# core.net
KiCad netlist of a schematic drawn in Altium Designer
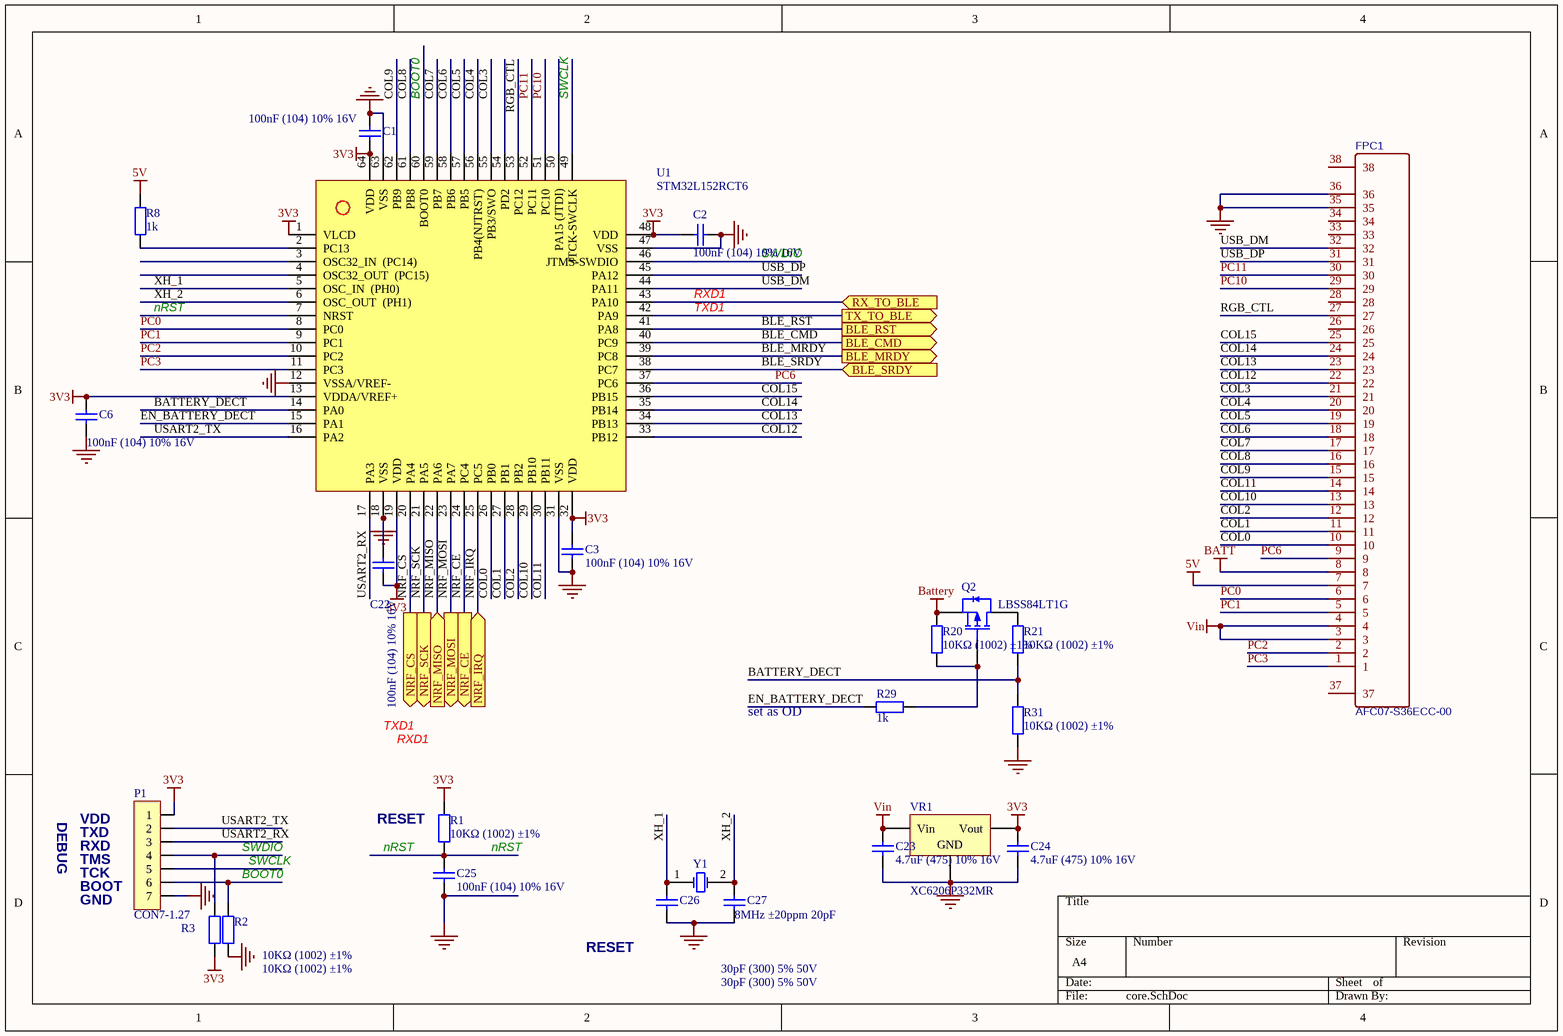
[diagram p0: core.SchDoc]

(export (version "E")
  (design (tool "Eeschema 10.0.6"))
  (components
    (comp (ref "C1")
      (value "100nF (104) 10% 16V")
      (footprint "0402_C")
      (description "贴片电容")
      (libsource (lib "Miscellaneous Devices LC") (part "0402 100nF (104) 10% 16V"))
    )
    (comp (ref "C2")
      (value "100nF (104) 10% 16V")
      (footprint "0402_C")
      (description "贴片电容")
      (libsource (lib "Miscellaneous Devices LC") (part "0402 100nF (104) 10% 16V"))
    )
    (comp (ref "C3")
      (value "100nF (104) 10% 16V")
      (footprint "0402_C")
      (description "贴片电容")
      (libsource (lib "Miscellaneous Devices LC") (part "0402 100nF (104) 10% 16V"))
    )
    (comp (ref "C6")
      (value "100nF (104) 10% 16V")
      (footprint "0402_C")
      (description "贴片电容")
      (libsource (lib "Miscellaneous Devices LC") (part "0402 100nF (104) 10% 16V"))
    )
    (comp (ref "C22")
      (value "100nF (104) 10% 16V")
      (footprint "0402_C")
      (description "贴片电容")
      (libsource (lib "Miscellaneous Devices LC") (part "0402 100nF (104) 10% 16V"))
    )
    (comp (ref "C23")
      (value "4.7uF (475) 10% 16V")
      (footprint "0603_C")
      (description "贴片电容")
      (libsource (lib "Miscellaneous Devices LC") (part "0603 4.7uF (475) 10% 16V"))
    )
    (comp (ref "C24")
      (value "4.7uF (475) 10% 16V")
      (footprint "0603_C")
      (description "贴片电容")
      (libsource (lib "Miscellaneous Devices LC") (part "0603 4.7uF (475) 10% 16V"))
    )
    (comp (ref "C25")
      (value "100nF (104) 10% 16V")
      (footprint "0402_C")
      (description "贴片电容")
      (libsource (lib "Miscellaneous Devices LC") (part "0402 100nF (104) 10% 16V"))
    )
    (comp (ref "C26")
      (value "30pF (300) 5% 50V")
      (footprint "0402_C")
      (description "贴片电容")
      (libsource (lib "Miscellaneous Devices LC") (part "0402 30pF (300) 5% 50V"))
    )
    (comp (ref "C27")
      (value "30pF (300) 5% 50V")
      (footprint "0402_C")
      (description "贴片电容")
      (libsource (lib "Miscellaneous Devices LC") (part "0402 30pF (300) 5% 50V"))
    )
    (comp (ref "FPC1")
      (value "AFC07-S36ECC-00")
      (footprint "FPC-0.5MM-36P-LCS-SJ-H2.0")
      (fields (field (name "BOM_SUPPLIER PART") "C262254") (field (name "CONTRIBUTOR") "LCSC"))
      (libsource (lib "tsl_Schlib") (part "AFC07-S36ECC-00"))
    )
    (comp (ref "P1")
      (value "CON7-1.27")
      (footprint "PH_7PIN_1.25_H-2")
      (description "直插插座")
      (fields (field (name "PART NUMBER") "RP02.07.000049") (field (name "PUBLISHER") "ChenYinaho"))
      (libsource (lib "tsl_Schlib") (part "CON7"))
    )
    (comp (ref "Q2")
      (value "LBSS84LT1G")
      (footprint "sot-23")
      (description "P-MOSFET -50V,-0.13A,10Ω@-5V")
      (fields
        (field (name "MANUFACTURER") "LRC(乐山无线电)")
        (field (name "PART NUMBER") "NEW")
        (field (name "PUBLISHER") "ChenYinaho")
      )
      (libsource (lib "tsl_Schlib") (part "P-MOS_BSS84"))
    )
    (comp (ref "R1")
      (value "10KΩ (1002) ±1%")
      (footprint "0402_R")
      (description "贴片电阻")
      (libsource (lib "Miscellaneous Devices LC") (part "0402 10KΩ (1002) 1%"))
    )
    (comp (ref "R2")
      (value "10KΩ (1002) ±1%")
      (footprint "0402_R")
      (description "贴片电阻")
      (libsource (lib "Miscellaneous Devices LC") (part "0402 10KΩ (1002) 1%"))
    )
    (comp (ref "R3")
      (value "10KΩ (1002) ±1%")
      (footprint "0402_R")
      (description "贴片电阻")
      (libsource (lib "Miscellaneous Devices LC") (part "0402 10KΩ (1002) 1%"))
    )
    (comp (ref "R8")
      (value "1k")
      (footprint "0402_R")
      (description "表贴电阻,0402,±1%,1/16W")
      (fields (field (name "PART NUMBER") "RP02.03.000161") (field (name "PUBLISHER") "ChenYinaho"))
      (libsource (lib "") (part "Res-0402_1k_1"))
    )
    (comp (ref "R20")
      (value "10KΩ (1002) ±1%")
      (footprint "0402_R")
      (description "贴片电阻")
      (libsource (lib "Miscellaneous Devices LC") (part "0402 10KΩ (1002) 1%"))
    )
    (comp (ref "R21")
      (value "10KΩ (1002) ±1%")
      (footprint "0402_R")
      (description "贴片电阻")
      (libsource (lib "Miscellaneous Devices LC") (part "0402 10KΩ (1002) 1%"))
    )
    (comp (ref "R29")
      (value "1k")
      (footprint "0402_R")
      (description "表贴电阻,0402,±1%,1/16W")
      (fields (field (name "PART NUMBER") "RP02.03.000161") (field (name "PUBLISHER") "ChenYinaho"))
      (libsource (lib "tsl_Schlib") (part "Res-0402_1k"))
    )
    (comp (ref "R31")
      (value "10KΩ (1002) ±1%")
      (footprint "0402_R")
      (description "贴片电阻")
      (libsource (lib "Miscellaneous Devices LC") (part "0402 10KΩ (1002) 1%"))
    )
    (comp (ref "U1")
      (value "STM32L152RCT6")
      (footprint "LQFP64")
      (description "MCU IC")
      (fields
        (field (name "MANUFACTURER") "ST")
        (field (name "PART NUMBER") "NEW")
        (field (name "PUBLISHER") "ChenYinaho")
      )
      (libsource (lib "tsl_Schlib") (part "STM32L152RCT"))
    )
    (comp (ref "VR1")
      (value "XC6206P332MR")
      (footprint "SOT-23-3L")
      (description "低压差线性稳压(LDO)")
      (libsource (lib "Miscellaneous Devices LC") (part "SOT-23 XC6206P332MR"))
    )
    (comp (ref "Y1")
      (value "8MHz ±20ppm 20pF")
      (footprint "SMD-5032_2P")
      (description "贴片晶振")
      (libsource (lib "Miscellaneous Devices LC") (part "SMD-5032_2P 8MHz 20ppm 20pF"))
    )
  )
  (nets
    (net (code "1") (name "/BATTERY_DECT") (class "Default")
      (node (ref "R21") (pin "1") (pinfunction "1_1") (pintype "passive"))
      (node (ref "R31") (pin "2") (pinfunction "2_2") (pintype "passive"))
      (node (ref "U1") (pin "14") (pinfunction "PA0_14") (pintype "passive"))
    )
    (net (code "2") (name "/BLE_CMD") (class "Default")
      (node (ref "U1") (pin "40") (pinfunction "PC9_40") (pintype "passive"))
    )
    (net (code "3") (name "/BLE_MRDY") (class "Default")
      (node (ref "U1") (pin "39") (pinfunction "PC8_39") (pintype "passive"))
    )
    (net (code "4") (name "/BLE_RST") (class "Default")
      (node (ref "U1") (pin "41") (pinfunction "PA8_41") (pintype "passive"))
    )
    (net (code "5") (name "/BLE_SRDY") (class "Default")
      (node (ref "U1") (pin "38") (pinfunction "PC7_38") (pintype "passive"))
    )
    (net (code "6") (name "/BOOT0") (class "Default")
      (node (ref "P1") (pin "6") (pinfunction "6_6") (pintype "passive"))
      (node (ref "R2") (pin "2") (pinfunction "2_2") (pintype "passive"))
      (node (ref "U1") (pin "60") (pinfunction "BOOT0_60") (pintype "passive"))
    )
    (net (code "7") (name "/COL0") (class "Default")
      (node (ref "FPC1") (pin "10") (pinfunction "10_10") (pintype "passive"))
      (node (ref "U1") (pin "26") (pinfunction "PB0_26") (pintype "passive"))
    )
    (net (code "8") (name "/COL1") (class "Default")
      (node (ref "FPC1") (pin "11") (pinfunction "11_11") (pintype "passive"))
      (node (ref "U1") (pin "27") (pinfunction "PB1_27") (pintype "passive"))
    )
    (net (code "9") (name "/COL2") (class "Default")
      (node (ref "FPC1") (pin "12") (pinfunction "12_12") (pintype "passive"))
      (node (ref "U1") (pin "28") (pinfunction "PB2_28") (pintype "passive"))
    )
    (net (code "10") (name "/COL3") (class "Default")
      (node (ref "FPC1") (pin "21") (pinfunction "21_21") (pintype "passive"))
      (node (ref "U1") (pin "55") (pinfunction "PB3/SWO_55") (pintype "passive"))
    )
    (net (code "11") (name "/COL4") (class "Default")
      (node (ref "FPC1") (pin "20") (pinfunction "20_20") (pintype "passive"))
      (node (ref "U1") (pin "56") (pinfunction "PB4(NJTRST)_56") (pintype "passive"))
    )
    (net (code "12") (name "/COL5") (class "Default")
      (node (ref "FPC1") (pin "19") (pinfunction "19_19") (pintype "passive"))
      (node (ref "U1") (pin "57") (pinfunction "PB5_57") (pintype "passive"))
    )
    (net (code "13") (name "/COL6") (class "Default")
      (node (ref "FPC1") (pin "18") (pinfunction "18_18") (pintype "passive"))
      (node (ref "U1") (pin "58") (pinfunction "PB6_58") (pintype "passive"))
    )
    (net (code "14") (name "/COL7") (class "Default")
      (node (ref "FPC1") (pin "17") (pinfunction "17_17") (pintype "passive"))
      (node (ref "U1") (pin "59") (pinfunction "PB7_59") (pintype "passive"))
    )
    (net (code "15") (name "/COL8") (class "Default")
      (node (ref "FPC1") (pin "16") (pinfunction "16_16") (pintype "passive"))
      (node (ref "U1") (pin "61") (pinfunction "PB8_61") (pintype "passive"))
    )
    (net (code "16") (name "/COL9") (class "Default")
      (node (ref "FPC1") (pin "15") (pinfunction "15_15") (pintype "passive"))
      (node (ref "U1") (pin "62") (pinfunction "PB9_62") (pintype "passive"))
    )
    (net (code "17") (name "/COL10") (class "Default")
      (node (ref "FPC1") (pin "13") (pinfunction "13_13") (pintype "passive"))
      (node (ref "U1") (pin "29") (pinfunction "PB10_29") (pintype "passive"))
    )
    (net (code "18") (name "/COL11") (class "Default")
      (node (ref "FPC1") (pin "14") (pinfunction "14_14") (pintype "passive"))
      (node (ref "U1") (pin "30") (pinfunction "PB11_30") (pintype "passive"))
    )
    (net (code "19") (name "/COL12") (class "Default")
      (node (ref "FPC1") (pin "22") (pinfunction "22_22") (pintype "passive"))
      (node (ref "U1") (pin "33") (pinfunction "PB12_33") (pintype "passive"))
    )
    (net (code "20") (name "/COL13") (class "Default")
      (node (ref "FPC1") (pin "23") (pinfunction "23_23") (pintype "passive"))
      (node (ref "U1") (pin "34") (pinfunction "PB13_34") (pintype "passive"))
    )
    (net (code "21") (name "/COL14") (class "Default")
      (node (ref "FPC1") (pin "24") (pinfunction "24_24") (pintype "passive"))
      (node (ref "U1") (pin "35") (pinfunction "PB14_35") (pintype "passive"))
    )
    (net (code "22") (name "/COL15") (class "Default")
      (node (ref "FPC1") (pin "25") (pinfunction "25_25") (pintype "passive"))
      (node (ref "U1") (pin "36") (pinfunction "PB15_36") (pintype "passive"))
    )
    (net (code "23") (name "/EN_BATTERY_DECT") (class "Default")
      (node (ref "R29") (pin "2") (pinfunction "2_2") (pintype "passive"))
      (node (ref "U1") (pin "15") (pinfunction "PA1_15") (pintype "passive"))
    )
    (net (code "24") (name "/NRF_CE") (class "Default")
      (node (ref "U1") (pin "24") (pinfunction "PC4_24") (pintype "passive"))
    )
    (net (code "25") (name "/NRF_CS") (class "Default")
      (node (ref "U1") (pin "20") (pinfunction "PA4_20") (pintype "passive"))
    )
    (net (code "26") (name "/NRF_IRQ") (class "Default")
      (node (ref "U1") (pin "25") (pinfunction "PC5_25") (pintype "passive"))
    )
    (net (code "27") (name "/NRF_MISO") (class "Default")
      (node (ref "U1") (pin "22") (pinfunction "PA6_22") (pintype "passive"))
    )
    (net (code "28") (name "/NRF_MOSI") (class "Default")
      (node (ref "U1") (pin "23") (pinfunction "PA7_23") (pintype "passive"))
    )
    (net (code "29") (name "/NRF_SCK") (class "Default")
      (node (ref "U1") (pin "21") (pinfunction "PA5_21") (pintype "passive"))
    )
    (net (code "30") (name "/PC0") (class "Default")
      (node (ref "FPC1") (pin "6") (pinfunction "6_6") (pintype "passive"))
      (node (ref "U1") (pin "8") (pinfunction "PC0_8") (pintype "passive"))
    )
    (net (code "31") (name "/PC1") (class "Default")
      (node (ref "FPC1") (pin "5") (pinfunction "5_5") (pintype "passive"))
      (node (ref "U1") (pin "9") (pinfunction "PC1_9") (pintype "passive"))
    )
    (net (code "32") (name "/PC2") (class "Default")
      (node (ref "FPC1") (pin "2") (pinfunction "2_2") (pintype "passive"))
      (node (ref "U1") (pin "10") (pinfunction "PC2_10") (pintype "passive"))
    )
    (net (code "33") (name "/PC3") (class "Default")
      (node (ref "FPC1") (pin "1") (pinfunction "1_1") (pintype "passive"))
      (node (ref "U1") (pin "11") (pinfunction "PC3_11") (pintype "passive"))
    )
    (net (code "34") (name "/PC6") (class "Default")
      (node (ref "FPC1") (pin "9") (pinfunction "9_9") (pintype "passive"))
      (node (ref "U1") (pin "37") (pinfunction "PC6_37") (pintype "passive"))
    )
    (net (code "35") (name "/PC10") (class "Default")
      (node (ref "FPC1") (pin "29") (pinfunction "29_29") (pintype "passive"))
      (node (ref "U1") (pin "51") (pinfunction "PC10_51") (pintype "passive"))
    )
    (net (code "36") (name "/PC11") (class "Default")
      (node (ref "FPC1") (pin "30") (pinfunction "30_30") (pintype "passive"))
      (node (ref "U1") (pin "52") (pinfunction "PC11_52") (pintype "passive"))
    )
    (net (code "37") (name "/RGB_CTL") (class "Default")
      (node (ref "FPC1") (pin "27") (pinfunction "27_27") (pintype "passive"))
      (node (ref "U1") (pin "53") (pinfunction "PC12_53") (pintype "passive"))
    )
    (net (code "38") (name "/RXD1") (class "Default")
      (node (ref "U1") (pin "43") (pinfunction "PA10_43") (pintype "passive"))
    )
    (net (code "39") (name "/SWCLK") (class "Default")
      (node (ref "P1") (pin "5") (pinfunction "5_5") (pintype "passive"))
      (node (ref "U1") (pin "49") (pinfunction "JTCK-SWCLK_49") (pintype "passive"))
    )
    (net (code "40") (name "/SWDIO") (class "Default")
      (node (ref "P1") (pin "4") (pinfunction "4_4") (pintype "passive"))
      (node (ref "R3") (pin "2") (pinfunction "2_2") (pintype "passive"))
      (node (ref "U1") (pin "46") (pinfunction "JTMS-SWDIO_46") (pintype "passive"))
    )
    (net (code "41") (name "/TXD1") (class "Default")
      (node (ref "U1") (pin "42") (pinfunction "PA9_42") (pintype "passive"))
    )
    (net (code "42") (name "/USART2_RX") (class "Default")
      (node (ref "P1") (pin "3") (pinfunction "3_3") (pintype "passive"))
      (node (ref "U1") (pin "17") (pinfunction "PA3_17") (pintype "passive"))
    )
    (net (code "43") (name "/USART2_TX") (class "Default")
      (node (ref "P1") (pin "2") (pinfunction "2_2") (pintype "passive"))
      (node (ref "U1") (pin "16") (pinfunction "PA2_16") (pintype "passive"))
    )
    (net (code "44") (name "/USB_DM") (class "Default")
      (node (ref "FPC1") (pin "32") (pinfunction "32_32") (pintype "passive"))
      (node (ref "U1") (pin "44") (pinfunction "PA11_44") (pintype "passive"))
    )
    (net (code "45") (name "/USB_DP") (class "Default")
      (node (ref "FPC1") (pin "31") (pinfunction "31_31") (pintype "passive"))
      (node (ref "U1") (pin "45") (pinfunction "PA12_45") (pintype "passive"))
    )
    (net (code "46") (name "/XH_1") (class "Default")
      (node (ref "C26") (pin "2") (pinfunction "2_2") (pintype "passive"))
      (node (ref "U1") (pin "5") (pinfunction "OSC_IN__(PH0)_5") (pintype "passive"))
      (node (ref "Y1") (pin "1") (pinfunction "OSC1_1") (pintype "passive"))
    )
    (net (code "47") (name "/XH_2") (class "Default")
      (node (ref "C27") (pin "2") (pinfunction "2_2") (pintype "passive"))
      (node (ref "U1") (pin "6") (pinfunction "OSC_OUT__(PH1)_6") (pintype "passive"))
      (node (ref "Y1") (pin "2") (pinfunction "OSC2_2") (pintype "passive"))
    )
    (net (code "48") (name "/nRST") (class "Default")
      (node (ref "C25") (pin "2") (pinfunction "2_2") (pintype "passive"))
      (node (ref "R1") (pin "1") (pinfunction "1_1") (pintype "passive"))
      (node (ref "U1") (pin "7") (pinfunction "NRST_7") (pintype "passive"))
    )
    (net (code "49") (name "3V3") (class "Default")
      (node (ref "C1") (pin "1") (pinfunction "1_1") (pintype "passive"))
      (node (ref "C2") (pin "2") (pinfunction "2_2") (pintype "passive"))
      (node (ref "C22") (pin "1") (pinfunction "1_1") (pintype "passive"))
      (node (ref "C24") (pin "2") (pinfunction "2_2") (pintype "passive"))
      (node (ref "C3") (pin "2") (pinfunction "2_2") (pintype "passive"))
      (node (ref "C6") (pin "2") (pinfunction "2_2") (pintype "passive"))
      (node (ref "P1") (pin "1") (pinfunction "1_1") (pintype "passive"))
      (node (ref "R1") (pin "2") (pinfunction "2_2") (pintype "passive"))
      (node (ref "R3") (pin "1") (pinfunction "1_1") (pintype "passive"))
      (node (ref "U1") (pin "1") (pinfunction "VLCD_1") (pintype "passive"))
      (node (ref "U1") (pin "13") (pinfunction "VDDA/VREF+_13") (pintype "passive"))
      (node (ref "U1") (pin "19") (pinfunction "VDD_19") (pintype "passive"))
      (node (ref "U1") (pin "32") (pinfunction "VDD_32") (pintype "passive"))
      (node (ref "U1") (pin "48") (pinfunction "VDD_48") (pintype "passive"))
      (node (ref "U1") (pin "64") (pinfunction "VDD_64") (pintype "passive"))
      (node (ref "VR1") (pin "2") (pinfunction "Vout_2") (pintype "passive"))
    )
    (net (code "50") (name "5V") (class "Default")
      (node (ref "FPC1") (pin "7") (pinfunction "7_7") (pintype "passive"))
      (node (ref "R8") (pin "1") (pinfunction "1_1") (pintype "passive"))
    )
    (net (code "51") (name "BATT") (class "Default")
      (node (ref "FPC1") (pin "8") (pinfunction "8_8") (pintype "passive"))
    )
    (net (code "52") (name "Battery") (class "Default")
      (node (ref "Q2") (pin "2") (pinfunction "S_2") (pintype "passive"))
      (node (ref "R20") (pin "2") (pinfunction "2_2") (pintype "passive"))
    )
    (net (code "53") (name "GND") (class "Default")
      (node (ref "C1") (pin "2") (pinfunction "2_2") (pintype "passive"))
      (node (ref "C2") (pin "1") (pinfunction "1_1") (pintype "passive"))
      (node (ref "C22") (pin "2") (pinfunction "2_2") (pintype "passive"))
      (node (ref "C23") (pin "1") (pinfunction "1_1") (pintype "passive"))
      (node (ref "C24") (pin "1") (pinfunction "1_1") (pintype "passive"))
      (node (ref "C25") (pin "1") (pinfunction "1_1") (pintype "passive"))
      (node (ref "C26") (pin "1") (pinfunction "1_1") (pintype "passive"))
      (node (ref "C27") (pin "1") (pinfunction "1_1") (pintype "passive"))
      (node (ref "C3") (pin "1") (pinfunction "1_1") (pintype "passive"))
      (node (ref "C6") (pin "1") (pinfunction "1_1") (pintype "passive"))
      (node (ref "FPC1") (pin "35") (pinfunction "35_35") (pintype "passive"))
      (node (ref "FPC1") (pin "36") (pinfunction "36_36") (pintype "passive"))
      (node (ref "P1") (pin "7") (pinfunction "7_7") (pintype "passive"))
      (node (ref "R2") (pin "1") (pinfunction "1_1") (pintype "passive"))
      (node (ref "R31") (pin "1") (pinfunction "1_1") (pintype "passive"))
      (node (ref "U1") (pin "12") (pinfunction "VSSA/VREF-_12") (pintype "passive"))
      (node (ref "U1") (pin "18") (pinfunction "VSS_18") (pintype "passive"))
      (node (ref "U1") (pin "31") (pinfunction "VSS_31") (pintype "passive"))
      (node (ref "U1") (pin "47") (pinfunction "VSS_47") (pintype "passive"))
      (node (ref "U1") (pin "63") (pinfunction "VSS_63") (pintype "passive"))
      (node (ref "VR1") (pin "1") (pinfunction "GND_1") (pintype "passive"))
    )
    (net (code "54") (name "Net-(Q2-D)") (class "Default")
      (node (ref "Q2") (pin "3") (pinfunction "D_3") (pintype "passive"))
      (node (ref "R21") (pin "2") (pinfunction "2_2") (pintype "passive"))
    )
    (net (code "55") (name "Net-(Q2-G)") (class "Default")
      (node (ref "Q2") (pin "1") (pinfunction "G_1") (pintype "passive"))
      (node (ref "R20") (pin "1") (pinfunction "1_1") (pintype "passive"))
      (node (ref "R29") (pin "1") (pinfunction "1_1") (pintype "passive"))
    )
    (net (code "56") (name "Net-(U1-PC13)") (class "Default")
      (node (ref "R8") (pin "2") (pinfunction "2_2") (pintype "passive"))
      (node (ref "U1") (pin "2") (pinfunction "PC13_2") (pintype "passive"))
    )
    (net (code "57") (name "Vin") (class "Default")
      (node (ref "C23") (pin "2") (pinfunction "2_2") (pintype "passive"))
      (node (ref "FPC1") (pin "3") (pinfunction "3_3") (pintype "passive"))
      (node (ref "FPC1") (pin "4") (pinfunction "4_4") (pintype "passive"))
      (node (ref "VR1") (pin "3") (pinfunction "Vin_3") (pintype "passive"))
    )
    (net (code "58") (name "unconnected-(FPC1-Pad26)") (class "Default")
      (node (ref "FPC1") (pin "26") (pinfunction "26_26") (pintype "passive"))
    )
    (net (code "59") (name "unconnected-(FPC1-Pad28)") (class "Default")
      (node (ref "FPC1") (pin "28") (pinfunction "28_28") (pintype "passive"))
    )
    (net (code "60") (name "unconnected-(FPC1-Pad33)") (class "Default")
      (node (ref "FPC1") (pin "33") (pinfunction "33_33") (pintype "passive"))
    )
    (net (code "61") (name "unconnected-(FPC1-Pad34)") (class "Default")
      (node (ref "FPC1") (pin "34") (pinfunction "34_34") (pintype "passive"))
    )
    (net (code "62") (name "unconnected-(FPC1-Pad37)") (class "Default")
      (node (ref "FPC1") (pin "37") (pinfunction "37_37") (pintype "passive"))
    )
    (net (code "63") (name "unconnected-(FPC1-Pad38)") (class "Default")
      (node (ref "FPC1") (pin "38") (pinfunction "38_38") (pintype "passive"))
    )
    (net (code "64") (name "unconnected-(U1-OSC32_IN__(PC14)-Pad3)") (class "Default")
      (node (ref "U1") (pin "3") (pinfunction "OSC32_IN__(PC14)_3") (pintype "passive"))
    )
    (net (code "65") (name "unconnected-(U1-OSC32_OUT__(PC15)-Pad4)") (class "Default")
      (node (ref "U1") (pin "4") (pinfunction "OSC32_OUT__(PC15)_4") (pintype "passive"))
    )
    (net (code "66") (name "unconnected-(U1-PA15_(JTDI)-Pad50)") (class "Default")
      (node (ref "U1") (pin "50") (pinfunction "PA15_(JTDI)_50") (pintype "passive"))
    )
    (net (code "67") (name "unconnected-(U1-PD2-Pad54)") (class "Default")
      (node (ref "U1") (pin "54") (pinfunction "PD2_54") (pintype "passive"))
    )
  )
)
